# RTM_Connectors.net
KiCad netlist of a schematic drawn in Altium Designer
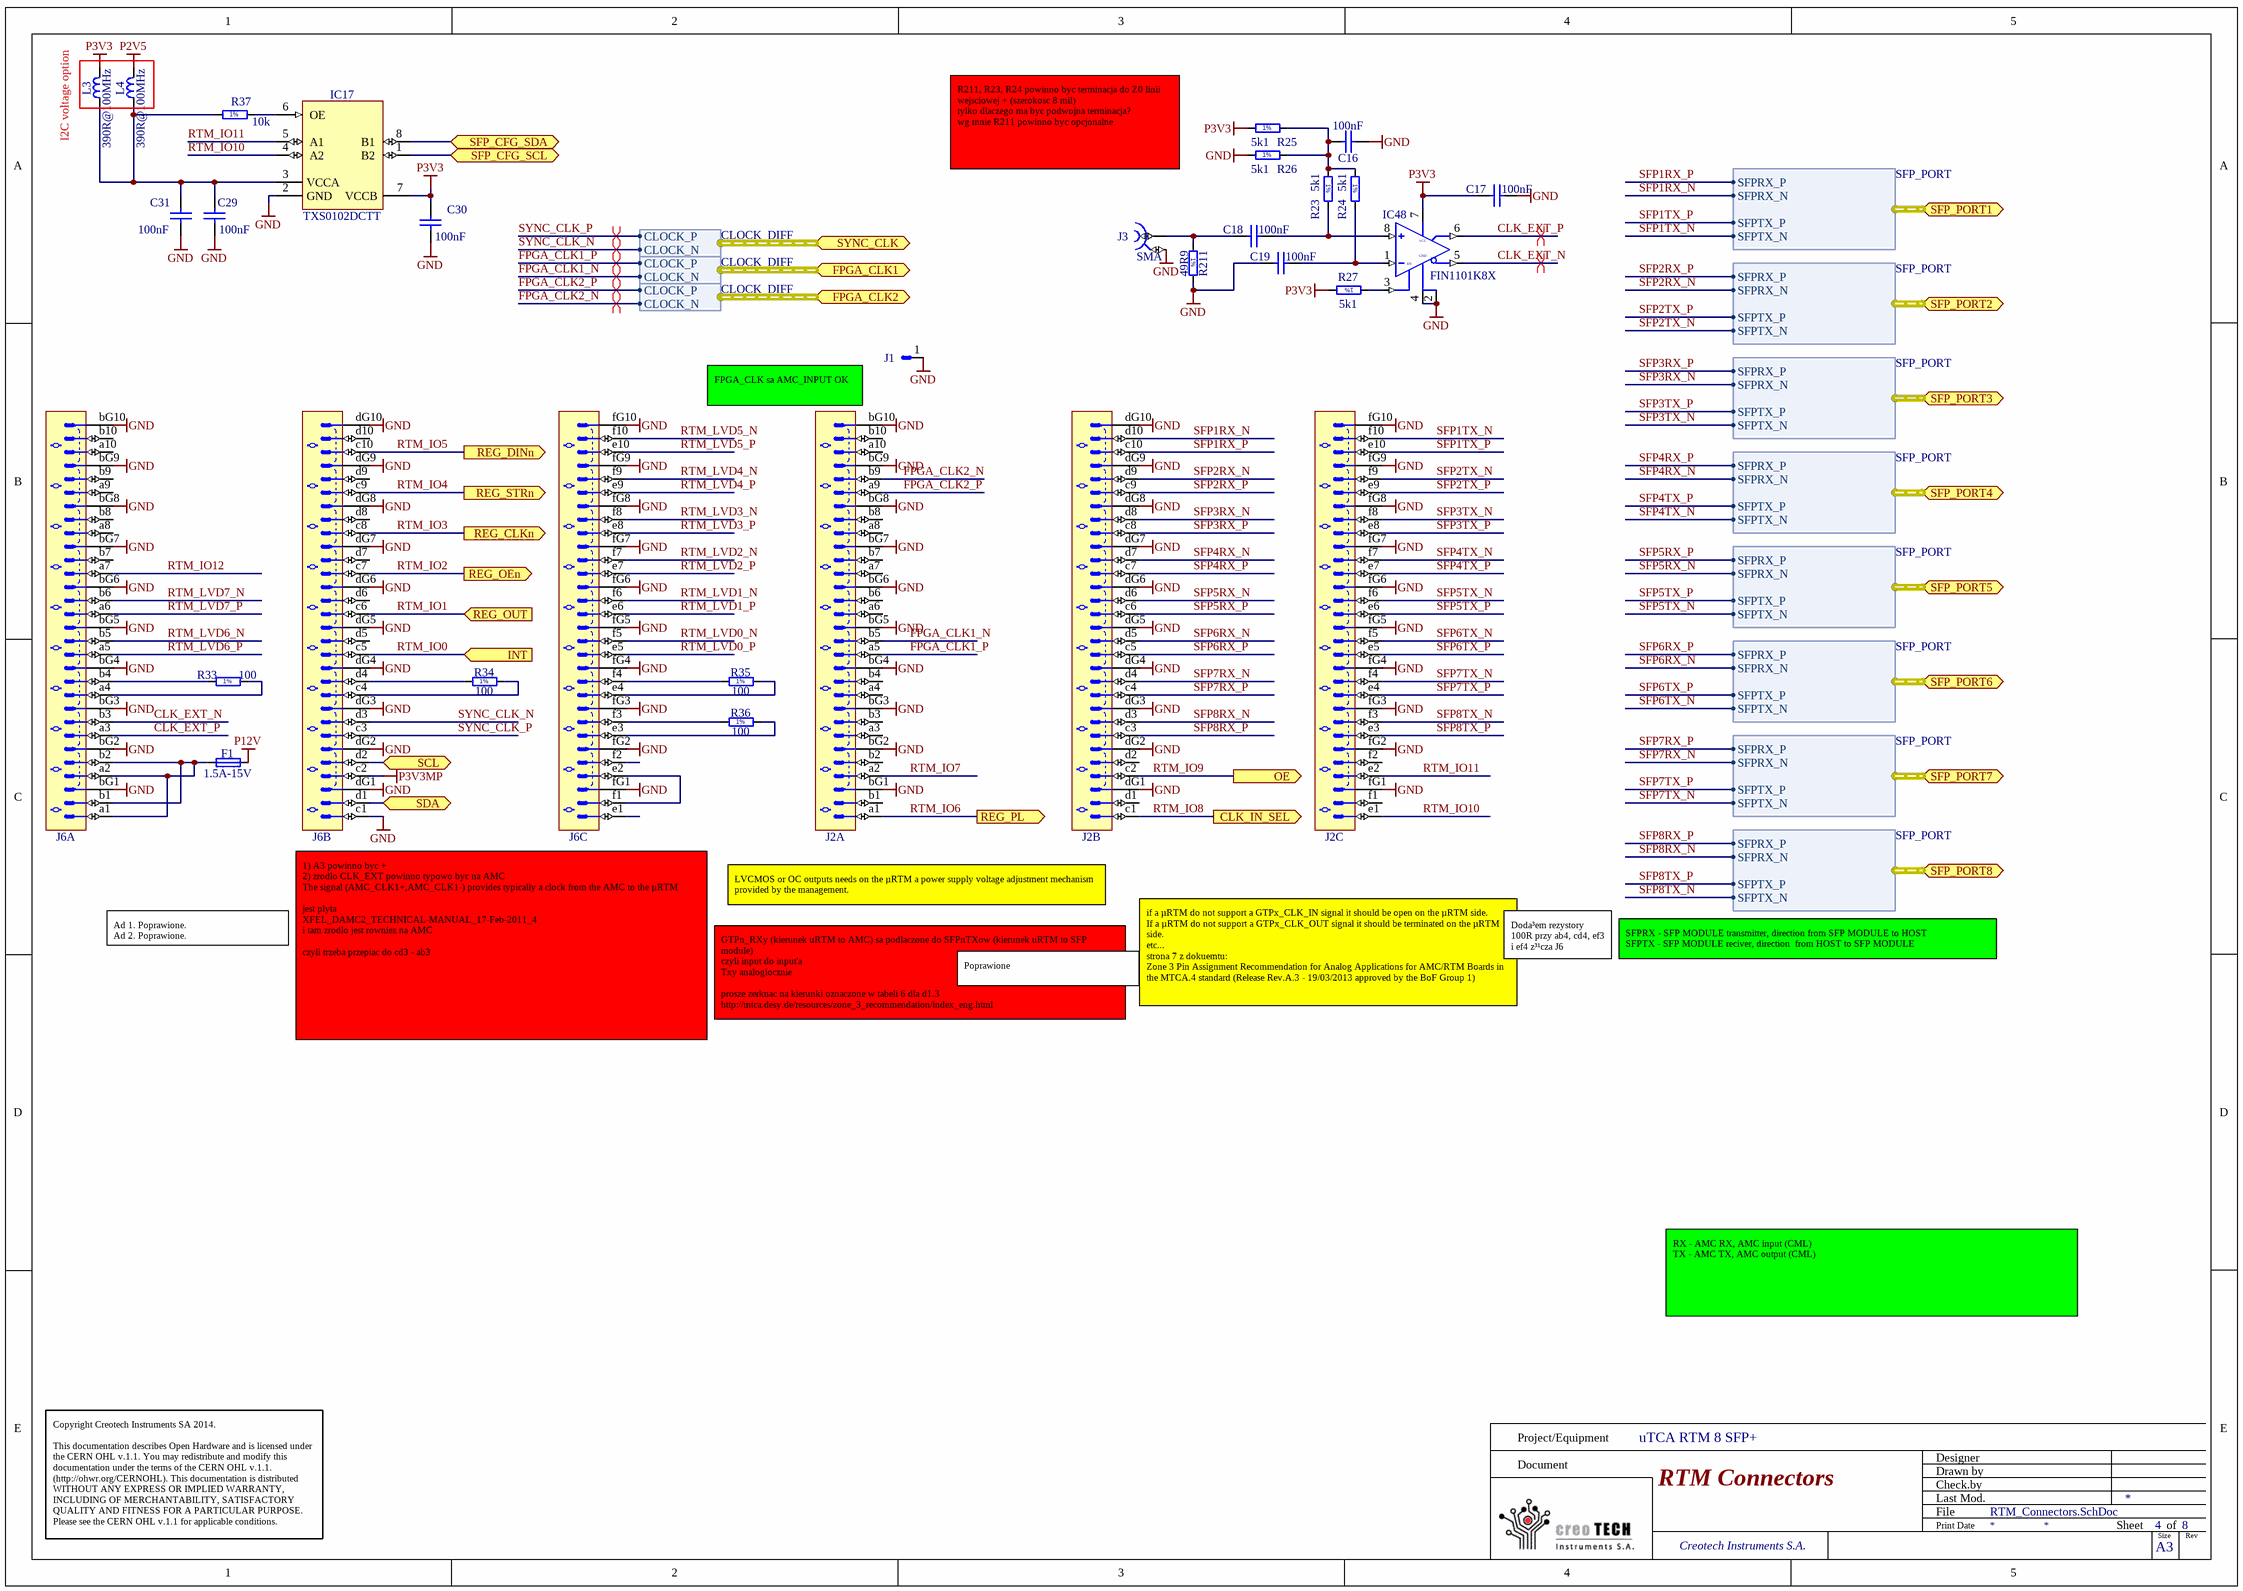
[diagram p0: RTM_Connectors.SchDoc]

(export (version "E")
  (design (tool "Eeschema 10.0.6"))
  (components
    (comp (ref "C16")
      (value "100nF")
      (footprint "CAPC1005X55N")
      (description "Non-polarised capacitor")
      (fields
        (field (name "PART NUMBER") "CC0402_100NF_16V_10%_X7R")
        (field (name "VOLTAGE") "16V")
        (field (name "AUTHOR") "CERN DEM JLC")
      )
      (libsource (lib "Capacitors") (part "Capacitor - non polarized"))
    )
    (comp (ref "C17")
      (value "100nF")
      (footprint "CAPC1005X55N")
      (description "Non-polarised capacitor")
      (fields
        (field (name "PART NUMBER") "CC0402_100NF_16V_10%_X7R")
        (field (name "VOLTAGE") "16V")
        (field (name "AUTHOR") "CERN DEM JLC")
      )
      (libsource (lib "Capacitors") (part "Capacitor - non polarized"))
    )
    (comp (ref "C18")
      (value "100nF")
      (footprint "CAPC1005X55N")
      (description "Non-polarised capacitor")
      (fields
        (field (name "PART NUMBER") "CC0402_100NF_16V_10%_X7R")
        (field (name "VOLTAGE") "16V")
        (field (name "AUTHOR") "CERN DEM JLC")
      )
      (libsource (lib "Capacitors") (part "Capacitor - non polarized"))
    )
    (comp (ref "C19")
      (value "100nF")
      (footprint "CAPC1005X55N")
      (description "Non-polarised capacitor")
      (fields
        (field (name "PART NUMBER") "CC0402_100NF_16V_10%_X7R")
        (field (name "VOLTAGE") "16V")
        (field (name "AUTHOR") "CERN DEM JLC")
      )
      (libsource (lib "Capacitors") (part "Capacitor - non polarized"))
    )
    (comp (ref "C29")
      (value "100nF")
      (footprint "CAPC0603X33N")
      (description "Non-polarised capacitor")
      (fields
        (field (name "PART NUMBER") "CC0201_100NF_6.3V_10%_X5R")
        (field (name "VOLTAGE") "6.3V")
        (field (name "AUTHOR") "CERN DEM JLC")
      )
      (libsource (lib "Capacitors") (part "Capacitor - non polarized"))
    )
    (comp (ref "C30")
      (value "100nF")
      (footprint "CAPC0603X33N")
      (description "Non-polarised capacitor")
      (fields
        (field (name "PART NUMBER") "CC0201_100NF_6.3V_10%_X5R")
        (field (name "VOLTAGE") "6.3V")
        (field (name "AUTHOR") "CERN DEM JLC")
      )
      (libsource (lib "Capacitors") (part "Capacitor - non polarized"))
    )
    (comp (ref "C31")
      (value "100nF")
      (footprint "CAPC0603X33N")
      (description "Non-polarised capacitor")
      (fields
        (field (name "PART NUMBER") "CC0201_100NF_6.3V_10%_X5R")
        (field (name "VOLTAGE") "6.3V")
        (field (name "AUTHOR") "CERN DEM JLC")
      )
      (libsource (lib "Capacitors") (part "Capacitor - non polarized"))
    )
    (comp (ref "F1")
      (value "1.5A-15V")
      (footprint "FUSR_TYCO_SMD150F-2")
      (description "Fuse")
      (fields
        (field (name "PART NUMBER") "FUSR_TYCO_SMD150F-2")
        (field (name "MANUFACTURER") "TYCO ELECTRONICS")
        (field (name "AUTHOR") "CERN DEM JLC")
      )
      (libsource (lib "Eletro-mechanical") (part "Fuse"))
    )
    (comp (ref "IC17")
      (value "TXS0102DCTT")
      (footprint "SOP65P400X130-8N")
      (description "2-Bit Bidirectionnal Voltage-Level Translator for Open-Drain And Push-Pull Applications")
      (fields (field (name "MANUFACTURER") "TEXAS INSTRUMENTS") (field (name "AUTHOR") "CERN DEM JLC"))
      (libsource (lib "ICs And Semiconductors") (part "TXS0102DCT"))
    )
    (comp (ref "IC48")
      (value "FIN1101K8X")
      (footprint "SOP50P310X90-8N")
      (description "LVDS Single Port High Speed Repeater")
      (fields (field (name "MANUFACTURER") "Fairchild") (field (name "AUTHOR") "LNLS DIG GBMB"))
      (libsource (lib "ICs And Semiconductors") (part "FIN1101"))
    )
    (comp (ref "J1")
      (value "~")
      (footprint "TYCO_1469265-1")
      (description "Single Pin Male")
      (fields
        (field (name "PART NUMBER") "TYCO_1469265-1")
        (field (name "MANUFACTURER") "TYCO ELECTRONICS")
        (field (name "AUTHOR") "CERN DEM JLC")
      )
      (libsource (lib "Connectors") (part "Single Pin Male"))
    )
    (comp (ref "J2")
      (value "~")
      (footprint "TYCO_6469183-1")
      (description "Connector 60 ATCA Male 30 Pairs (60 Signals) + 3x10 Ground")
      (fields
        (field (name "PART NUMBER") "TYCO_6469183-1")
        (field (name "MANUFACTURER") "TYCO ELECTRONICS")
        (field (name "AUTHOR") "CERN DEM JLC")
      )
      (libsource (lib "Connectors") (part "Connector ATCA 60+30 Male"))
    )
    (comp (ref "J3")
      (value "SMA")
      (footprint "HUBER-SUHNER_85_SMA-50-0-101/111_NE")
      (fields
        (field (name "PART NUMBER") "HUBER-SUHNER_85_SMA-50-0-101/111_NE")
        (field (name "MANUFACTURER") "HUBER+SUHNER")
        (field (name "MANUFACTURER PART NUMBER") "85_SMA-50-0-101/111_NE")
        (field (name "AUTHOR") "CERN DEM JLC")
      )
      (libsource (lib "Connectors") (part "Coax_1Female_1Shield"))
    )
    (comp (ref "J6")
      (value "~")
      (footprint "TYCO_6469183-1")
      (description "Connector 60 ATCA Male 30 Pairs (60 Signals) + 3x10 Ground")
      (fields
        (field (name "PART NUMBER") "TYCO_6469183-1")
        (field (name "MANUFACTURER") "TYCO ELECTRONICS")
        (field (name "AUTHOR") "CERN DEM JLC")
      )
      (libsource (lib "Connectors") (part "Connector ATCA 60+30 Male"))
    )
    (comp (ref "L3")
      (value "390R@100MHz")
      (footprint "INDC1608X95N")
      (description "Inductor")
      (fields
        (field (name "PART NUMBER") "IND0603_TDK_MPZ1608R391A")
        (field (name "POWER") "1.2A")
        (field (name "AUTHOR") "CERN DEM JLC")
      )
      (libsource (lib "Inductors & Transformers") (part "Inductor"))
    )
    (comp (ref "L4")
      (value "390R@100MHz")
      (footprint "INDC1608X95N")
      (description "Inductor")
      (fields
        (field (name "PART NUMBER") "IND0603_TDK_MPZ1608R391A")
        (field (name "POWER") "1.2A")
        (field (name "AUTHOR") "CERN DEM JLC")
      )
      (libsource (lib "Inductors & Transformers") (part "Inductor"))
    )
    (comp (ref "R23")
      (value "5k1")
      (footprint "RESC1608X55N")
      (description "Resistor - 1%")
      (fields
        (field (name "PART NUMBER") "R0603_5K1_1%_0.1W_100PPM")
        (field (name "POWER") "0.1W")
        (field (name "AUTHOR") "CERN DEM JLC")
      )
      (libsource (lib "Resistors") (part "Resistor - 1%"))
    )
    (comp (ref "R24")
      (value "5k1")
      (footprint "RESC1608X55N")
      (description "Resistor - 1%")
      (fields
        (field (name "PART NUMBER") "R0603_5K1_1%_0.1W_100PPM")
        (field (name "POWER") "0.1W")
        (field (name "AUTHOR") "CERN DEM JLC")
      )
      (libsource (lib "Resistors") (part "Resistor - 1%"))
    )
    (comp (ref "R25")
      (value "5k1")
      (footprint "RESC1608X55N")
      (description "Resistor - 1%")
      (fields
        (field (name "PART NUMBER") "R0603_5K1_1%_0.1W_100PPM")
        (field (name "POWER") "0.1W")
        (field (name "AUTHOR") "CERN DEM JLC")
      )
      (libsource (lib "Resistors") (part "Resistor - 1%"))
    )
    (comp (ref "R26")
      (value "5k1")
      (footprint "RESC1608X55N")
      (description "Resistor - 1%")
      (fields
        (field (name "PART NUMBER") "R0603_5K1_1%_0.1W_100PPM")
        (field (name "POWER") "0.1W")
        (field (name "AUTHOR") "CERN DEM JLC")
      )
      (libsource (lib "Resistors") (part "Resistor - 1%"))
    )
    (comp (ref "R27")
      (value "5k1")
      (footprint "RESC1608X55N")
      (description "Resistor - 1%")
      (fields
        (field (name "PART NUMBER") "R0603_5K1_1%_0.1W_100PPM")
        (field (name "POWER") "0.1W")
        (field (name "AUTHOR") "CERN DEM JLC")
      )
      (libsource (lib "Resistors") (part "Resistor - 1%"))
    )
    (comp (ref "R33")
      (value "100")
      (footprint "RESC1608X55N")
      (description "Resistor - 1%")
      (fields
        (field (name "PART NUMBER") "R0603_100R_1%_0.1W_100PPM")
        (field (name "POWER") "0.1W")
        (field (name "AUTHOR") "CERN DEM JLC")
      )
      (libsource (lib "Resistors") (part "Resistor - 1%"))
    )
    (comp (ref "R34")
      (value "100")
      (footprint "RESC1608X55N")
      (description "Resistor - 1%")
      (fields
        (field (name "PART NUMBER") "R0603_100R_1%_0.1W_100PPM")
        (field (name "POWER") "0.1W")
        (field (name "AUTHOR") "CERN DEM JLC")
      )
      (libsource (lib "Resistors") (part "Resistor - 1%"))
    )
    (comp (ref "R35")
      (value "100")
      (footprint "RESC1608X55N")
      (description "Resistor - 1%")
      (fields
        (field (name "PART NUMBER") "R0603_100R_1%_0.1W_100PPM")
        (field (name "POWER") "0.1W")
        (field (name "AUTHOR") "CERN DEM JLC")
      )
      (libsource (lib "Resistors") (part "Resistor - 1%"))
    )
    (comp (ref "R36")
      (value "100")
      (footprint "RESC1608X55N")
      (description "Resistor - 1%")
      (fields
        (field (name "PART NUMBER") "R0603_100R_1%_0.1W_100PPM")
        (field (name "POWER") "0.1W")
        (field (name "AUTHOR") "CERN DEM JLC")
      )
      (libsource (lib "Resistors") (part "Resistor - 1%"))
    )
    (comp (ref "R37")
      (value "10k")
      (footprint "RESC1005X40N")
      (description "Resistor - 1%")
      (fields
        (field (name "PART NUMBER") "R0402_10K_1%_0.0625W_100PPM")
        (field (name "POWER") "0.0625W")
        (field (name "AUTHOR") "CERN DEM JLC")
      )
      (libsource (lib "Resistors") (part "Resistor - 1%"))
    )
    (comp (ref "R211")
      (value "49R9")
      (footprint "RESC1005X40N")
      (description "Resistor - 1%")
      (fields
        (field (name "PART NUMBER") "R0402_49R9_1%_0.0625W_100PPM")
        (field (name "POWER") "0.0625W")
        (field (name "AUTHOR") "CERN DEM JLC")
      )
      (libsource (lib "Resistors") (part "Resistor - 1%"))
    )
  )
  (nets
    (net (code "3") (name "/CLK_EXT_N") (class "Default")
      (node (ref "IC48") (pin "5") (pinfunction "~{Q}_5") (pintype "output"))
      (node (ref "J6") (pin "b3") (pinfunction "b3_b3") (pintype "bidirectional"))
    )
    (net (code "4") (name "/CLK_EXT_P") (class "Default")
      (node (ref "IC48") (pin "6") (pinfunction "Q_6") (pintype "output"))
      (node (ref "J6") (pin "a3") (pinfunction "a3_a3") (pintype "bidirectional"))
    )
    (net (code "5") (name "/FPGA_CLK1_N") (class "Default")
      (node (ref "J2") (pin "b5") (pinfunction "b5_b5") (pintype "bidirectional"))
    )
    (net (code "6") (name "/FPGA_CLK1_P") (class "Default")
      (node (ref "J2") (pin "a5") (pinfunction "a5_a5") (pintype "bidirectional"))
    )
    (net (code "7") (name "/FPGA_CLK2_N") (class "Default")
      (node (ref "J2") (pin "b9") (pinfunction "b9_b9") (pintype "bidirectional"))
    )
    (net (code "8") (name "/FPGA_CLK2_P") (class "Default")
      (node (ref "J2") (pin "a9") (pinfunction "a9_a9") (pintype "bidirectional"))
    )
    (net (code "9") (name "/RTM_IO0") (class "Default")
      (node (ref "J6") (pin "c5") (pinfunction "c5_c5") (pintype "bidirectional"))
    )
    (net (code "10") (name "/RTM_IO1") (class "Default")
      (node (ref "J6") (pin "c6") (pinfunction "c6_c6") (pintype "bidirectional"))
    )
    (net (code "11") (name "/RTM_IO2") (class "Default")
      (node (ref "J6") (pin "c7") (pinfunction "c7_c7") (pintype "bidirectional"))
    )
    (net (code "12") (name "/RTM_IO3") (class "Default")
      (node (ref "J6") (pin "c8") (pinfunction "c8_c8") (pintype "bidirectional"))
    )
    (net (code "13") (name "/RTM_IO4") (class "Default")
      (node (ref "J6") (pin "c9") (pinfunction "c9_c9") (pintype "bidirectional"))
    )
    (net (code "14") (name "/RTM_IO5") (class "Default")
      (node (ref "J6") (pin "c10") (pinfunction "c10_c10") (pintype "bidirectional"))
    )
    (net (code "15") (name "/RTM_IO6") (class "Default")
      (node (ref "J2") (pin "a1") (pinfunction "a1_a1") (pintype "bidirectional"))
    )
    (net (code "16") (name "/RTM_IO7") (class "Default")
      (node (ref "J2") (pin "a2") (pinfunction "a2_a2") (pintype "bidirectional"))
    )
    (net (code "17") (name "/RTM_IO8") (class "Default")
      (node (ref "J2") (pin "c1") (pinfunction "c1_c1") (pintype "bidirectional"))
    )
    (net (code "18") (name "/RTM_IO9") (class "Default")
      (node (ref "J2") (pin "c2") (pinfunction "c2_c2") (pintype "bidirectional"))
    )
    (net (code "19") (name "/RTM_IO10") (class "Default")
      (node (ref "IC17") (pin "4") (pinfunction "A2_4") (pintype "bidirectional"))
      (node (ref "J2") (pin "e1") (pinfunction "e1_e1") (pintype "bidirectional"))
    )
    (net (code "20") (name "/RTM_IO11") (class "Default")
      (node (ref "IC17") (pin "5") (pinfunction "A1_5") (pintype "bidirectional"))
      (node (ref "J2") (pin "e2") (pinfunction "e2_e2") (pintype "bidirectional"))
    )
    (net (code "21") (name "/RTM_IO12") (class "Default")
      (node (ref "J6") (pin "a7") (pinfunction "a7_a7") (pintype "bidirectional"))
    )
    (net (code "22") (name "/RTM_LVD0_N") (class "Default")
      (node (ref "J6") (pin "f5") (pinfunction "f5_f5") (pintype "bidirectional"))
    )
    (net (code "23") (name "/RTM_LVD0_P") (class "Default")
      (node (ref "J6") (pin "e5") (pinfunction "e5_e5") (pintype "bidirectional"))
    )
    (net (code "24") (name "/RTM_LVD1_N") (class "Default")
      (node (ref "J6") (pin "f6") (pinfunction "f6_f6") (pintype "bidirectional"))
    )
    (net (code "25") (name "/RTM_LVD1_P") (class "Default")
      (node (ref "J6") (pin "e6") (pinfunction "e6_e6") (pintype "bidirectional"))
    )
    (net (code "26") (name "/RTM_LVD2_N") (class "Default")
      (node (ref "J6") (pin "f7") (pinfunction "f7_f7") (pintype "bidirectional"))
    )
    (net (code "27") (name "/RTM_LVD2_P") (class "Default")
      (node (ref "J6") (pin "e7") (pinfunction "e7_e7") (pintype "bidirectional"))
    )
    (net (code "28") (name "/RTM_LVD3_N") (class "Default")
      (node (ref "J6") (pin "f8") (pinfunction "f8_f8") (pintype "bidirectional"))
    )
    (net (code "29") (name "/RTM_LVD3_P") (class "Default")
      (node (ref "J6") (pin "e8") (pinfunction "e8_e8") (pintype "bidirectional"))
    )
    (net (code "30") (name "/RTM_LVD4_N") (class "Default")
      (node (ref "J6") (pin "f9") (pinfunction "f9_f9") (pintype "bidirectional"))
    )
    (net (code "31") (name "/RTM_LVD4_P") (class "Default")
      (node (ref "J6") (pin "e9") (pinfunction "e9_e9") (pintype "bidirectional"))
    )
    (net (code "32") (name "/RTM_LVD5_N") (class "Default")
      (node (ref "J6") (pin "f10") (pinfunction "f10_f10") (pintype "bidirectional"))
    )
    (net (code "33") (name "/RTM_LVD5_P") (class "Default")
      (node (ref "J6") (pin "e10") (pinfunction "e10_e10") (pintype "bidirectional"))
    )
    (net (code "34") (name "/RTM_LVD6_N") (class "Default")
      (node (ref "J6") (pin "b5") (pinfunction "b5_b5") (pintype "bidirectional"))
    )
    (net (code "35") (name "/RTM_LVD6_P") (class "Default")
      (node (ref "J6") (pin "a5") (pinfunction "a5_a5") (pintype "bidirectional"))
    )
    (net (code "36") (name "/RTM_LVD7_N") (class "Default")
      (node (ref "J6") (pin "b6") (pinfunction "b6_b6") (pintype "bidirectional"))
    )
    (net (code "37") (name "/RTM_LVD7_P") (class "Default")
      (node (ref "J6") (pin "a6") (pinfunction "a6_a6") (pintype "bidirectional"))
    )
    (net (code "38") (name "/SCL") (class "Default")
      (node (ref "J6") (pin "d2") (pinfunction "d2_d2") (pintype "bidirectional"))
    )
    (net (code "39") (name "/SDA") (class "Default")
      (node (ref "J6") (pin "d1") (pinfunction "d1_d1") (pintype "bidirectional"))
    )
    (net (code "40") (name "/SFP1RX_N") (class "Default")
      (node (ref "J2") (pin "d10") (pinfunction "d10_d10") (pintype "bidirectional"))
    )
    (net (code "41") (name "/SFP1RX_P") (class "Default")
      (node (ref "J2") (pin "c10") (pinfunction "c10_c10") (pintype "bidirectional"))
    )
    (net (code "42") (name "/SFP1TX_N") (class "Default")
      (node (ref "J2") (pin "f10") (pinfunction "f10_f10") (pintype "bidirectional"))
    )
    (net (code "43") (name "/SFP1TX_P") (class "Default")
      (node (ref "J2") (pin "e10") (pinfunction "e10_e10") (pintype "bidirectional"))
    )
    (net (code "44") (name "/SFP2RX_N") (class "Default")
      (node (ref "J2") (pin "d9") (pinfunction "d9_d9") (pintype "bidirectional"))
    )
    (net (code "45") (name "/SFP2RX_P") (class "Default")
      (node (ref "J2") (pin "c9") (pinfunction "c9_c9") (pintype "bidirectional"))
    )
    (net (code "46") (name "/SFP2TX_N") (class "Default")
      (node (ref "J2") (pin "f9") (pinfunction "f9_f9") (pintype "bidirectional"))
    )
    (net (code "47") (name "/SFP2TX_P") (class "Default")
      (node (ref "J2") (pin "e9") (pinfunction "e9_e9") (pintype "bidirectional"))
    )
    (net (code "48") (name "/SFP3RX_N") (class "Default")
      (node (ref "J2") (pin "d8") (pinfunction "d8_d8") (pintype "bidirectional"))
    )
    (net (code "49") (name "/SFP3RX_P") (class "Default")
      (node (ref "J2") (pin "c8") (pinfunction "c8_c8") (pintype "bidirectional"))
    )
    (net (code "50") (name "/SFP3TX_N") (class "Default")
      (node (ref "J2") (pin "f8") (pinfunction "f8_f8") (pintype "bidirectional"))
    )
    (net (code "51") (name "/SFP3TX_P") (class "Default")
      (node (ref "J2") (pin "e8") (pinfunction "e8_e8") (pintype "bidirectional"))
    )
    (net (code "52") (name "/SFP4RX_N") (class "Default")
      (node (ref "J2") (pin "d7") (pinfunction "d7_d7") (pintype "bidirectional"))
    )
    (net (code "53") (name "/SFP4RX_P") (class "Default")
      (node (ref "J2") (pin "c7") (pinfunction "c7_c7") (pintype "bidirectional"))
    )
    (net (code "54") (name "/SFP4TX_N") (class "Default")
      (node (ref "J2") (pin "f7") (pinfunction "f7_f7") (pintype "bidirectional"))
    )
    (net (code "55") (name "/SFP4TX_P") (class "Default")
      (node (ref "J2") (pin "e7") (pinfunction "e7_e7") (pintype "bidirectional"))
    )
    (net (code "56") (name "/SFP5RX_N") (class "Default")
      (node (ref "J2") (pin "d6") (pinfunction "d6_d6") (pintype "bidirectional"))
    )
    (net (code "57") (name "/SFP5RX_P") (class "Default")
      (node (ref "J2") (pin "c6") (pinfunction "c6_c6") (pintype "bidirectional"))
    )
    (net (code "58") (name "/SFP5TX_N") (class "Default")
      (node (ref "J2") (pin "f6") (pinfunction "f6_f6") (pintype "bidirectional"))
    )
    (net (code "59") (name "/SFP5TX_P") (class "Default")
      (node (ref "J2") (pin "e6") (pinfunction "e6_e6") (pintype "bidirectional"))
    )
    (net (code "60") (name "/SFP6RX_N") (class "Default")
      (node (ref "J2") (pin "d5") (pinfunction "d5_d5") (pintype "bidirectional"))
    )
    (net (code "61") (name "/SFP6RX_P") (class "Default")
      (node (ref "J2") (pin "c5") (pinfunction "c5_c5") (pintype "bidirectional"))
    )
    (net (code "62") (name "/SFP6TX_N") (class "Default")
      (node (ref "J2") (pin "f5") (pinfunction "f5_f5") (pintype "bidirectional"))
    )
    (net (code "63") (name "/SFP6TX_P") (class "Default")
      (node (ref "J2") (pin "e5") (pinfunction "e5_e5") (pintype "bidirectional"))
    )
    (net (code "64") (name "/SFP7RX_N") (class "Default")
      (node (ref "J2") (pin "d4") (pinfunction "d4_d4") (pintype "bidirectional"))
    )
    (net (code "65") (name "/SFP7RX_P") (class "Default")
      (node (ref "J2") (pin "c4") (pinfunction "c4_c4") (pintype "bidirectional"))
    )
    (net (code "66") (name "/SFP7TX_N") (class "Default")
      (node (ref "J2") (pin "f4") (pinfunction "f4_f4") (pintype "bidirectional"))
    )
    (net (code "67") (name "/SFP7TX_P") (class "Default")
      (node (ref "J2") (pin "e4") (pinfunction "e4_e4") (pintype "bidirectional"))
    )
    (net (code "68") (name "/SFP8RX_N") (class "Default")
      (node (ref "J2") (pin "d3") (pinfunction "d3_d3") (pintype "bidirectional"))
    )
    (net (code "69") (name "/SFP8RX_P") (class "Default")
      (node (ref "J2") (pin "c3") (pinfunction "c3_c3") (pintype "bidirectional"))
    )
    (net (code "70") (name "/SFP8TX_N") (class "Default")
      (node (ref "J2") (pin "f3") (pinfunction "f3_f3") (pintype "bidirectional"))
    )
    (net (code "71") (name "/SFP8TX_P") (class "Default")
      (node (ref "J2") (pin "e3") (pinfunction "e3_e3") (pintype "bidirectional"))
    )
    (net (code "72") (name "/SFP_CFG_SCL") (class "Default")
      (node (ref "IC17") (pin "1") (pinfunction "B2_1") (pintype "bidirectional"))
    )
    (net (code "73") (name "/SFP_CFG_SDA") (class "Default")
      (node (ref "IC17") (pin "8") (pinfunction "B1_8") (pintype "bidirectional"))
    )
    (net (code "74") (name "/SYNC_CLK_N") (class "Default")
      (node (ref "J6") (pin "d3") (pinfunction "d3_d3") (pintype "bidirectional"))
    )
    (net (code "75") (name "/SYNC_CLK_P") (class "Default")
      (node (ref "J6") (pin "c3") (pinfunction "c3_c3") (pintype "bidirectional"))
    )
    (net (code "78") (name "GND") (class "Default")
      (node (ref "C16") (pin "2") (pinfunction "2_2") (pintype "passive"))
      (node (ref "C17") (pin "2") (pinfunction "2_2") (pintype "passive"))
      (node (ref "C19") (pin "1") (pinfunction "1_1") (pintype "passive"))
      (node (ref "C29") (pin "2") (pinfunction "2_2") (pintype "passive"))
      (node (ref "C30") (pin "2") (pinfunction "2_2") (pintype "passive"))
      (node (ref "C31") (pin "2") (pinfunction "2_2") (pintype "passive"))
      (node (ref "IC17") (pin "2") (pinfunction "GND_2") (pintype "power_in"))
      (node (ref "IC48") (pin "2") (pinfunction "GND_2") (pintype "power_in"))
      (node (ref "IC48") (pin "4") (pinfunction "GND_4") (pintype "power_in"))
      (node (ref "J1") (pin "1") (pinfunction "1_1") (pintype "bidirectional"))
      (node (ref "J2") (pin "bG1") (pinfunction "bG1_bG1") (pintype "power_in"))
      (node (ref "J2") (pin "bG10") (pinfunction "bG10_bG10") (pintype "power_in"))
      (node (ref "J2") (pin "bG2") (pinfunction "bG2_bG2") (pintype "power_in"))
      (node (ref "J2") (pin "bG3") (pinfunction "bG3_bG3") (pintype "power_in"))
      (node (ref "J2") (pin "bG4") (pinfunction "bG4_bG4") (pintype "power_in"))
      (node (ref "J2") (pin "bG5") (pinfunction "bG5_bG5") (pintype "power_in"))
      (node (ref "J2") (pin "bG6") (pinfunction "bG6_bG6") (pintype "power_in"))
      (node (ref "J2") (pin "bG7") (pinfunction "bG7_bG7") (pintype "power_in"))
      (node (ref "J2") (pin "bG8") (pinfunction "bG8_bG8") (pintype "power_in"))
      (node (ref "J2") (pin "bG9") (pinfunction "bG9_bG9") (pintype "power_in"))
      (node (ref "J2") (pin "dG1") (pinfunction "dG1_dG1") (pintype "power_in"))
      (node (ref "J2") (pin "dG10") (pinfunction "dG10_dG10") (pintype "power_in"))
      (node (ref "J2") (pin "dG2") (pinfunction "dG2_dG2") (pintype "power_in"))
      (node (ref "J2") (pin "dG3") (pinfunction "dG3_dG3") (pintype "power_in"))
      (node (ref "J2") (pin "dG4") (pinfunction "dG4_dG4") (pintype "power_in"))
      (node (ref "J2") (pin "dG5") (pinfunction "dG5_dG5") (pintype "power_in"))
      (node (ref "J2") (pin "dG6") (pinfunction "dG6_dG6") (pintype "power_in"))
      (node (ref "J2") (pin "dG7") (pinfunction "dG7_dG7") (pintype "power_in"))
      (node (ref "J2") (pin "dG8") (pinfunction "dG8_dG8") (pintype "power_in"))
      (node (ref "J2") (pin "dG9") (pinfunction "dG9_dG9") (pintype "power_in"))
      (node (ref "J2") (pin "fG1") (pinfunction "fG1_fG1") (pintype "power_in"))
      (node (ref "J2") (pin "fG10") (pinfunction "fG10_fG10") (pintype "power_in"))
      (node (ref "J2") (pin "fG2") (pinfunction "fG2_fG2") (pintype "power_in"))
      (node (ref "J2") (pin "fG3") (pinfunction "fG3_fG3") (pintype "power_in"))
      (node (ref "J2") (pin "fG4") (pinfunction "fG4_fG4") (pintype "power_in"))
      (node (ref "J2") (pin "fG5") (pinfunction "fG5_fG5") (pintype "power_in"))
      (node (ref "J2") (pin "fG6") (pinfunction "fG6_fG6") (pintype "power_in"))
      (node (ref "J2") (pin "fG7") (pinfunction "fG7_fG7") (pintype "power_in"))
      (node (ref "J2") (pin "fG8") (pinfunction "fG8_fG8") (pintype "power_in"))
      (node (ref "J2") (pin "fG9") (pinfunction "fG9_fG9") (pintype "power_in"))
      (node (ref "J3") (pin "2") (pinfunction "2_2") (pintype "bidirectional"))
      (node (ref "J6") (pin "bG1") (pinfunction "bG1_bG1") (pintype "power_in"))
      (node (ref "J6") (pin "bG10") (pinfunction "bG10_bG10") (pintype "power_in"))
      (node (ref "J6") (pin "bG2") (pinfunction "bG2_bG2") (pintype "power_in"))
      (node (ref "J6") (pin "bG3") (pinfunction "bG3_bG3") (pintype "power_in"))
      (node (ref "J6") (pin "bG4") (pinfunction "bG4_bG4") (pintype "power_in"))
      (node (ref "J6") (pin "bG5") (pinfunction "bG5_bG5") (pintype "power_in"))
      (node (ref "J6") (pin "bG6") (pinfunction "bG6_bG6") (pintype "power_in"))
      (node (ref "J6") (pin "bG7") (pinfunction "bG7_bG7") (pintype "power_in"))
      (node (ref "J6") (pin "bG8") (pinfunction "bG8_bG8") (pintype "power_in"))
      (node (ref "J6") (pin "bG9") (pinfunction "bG9_bG9") (pintype "power_in"))
      (node (ref "J6") (pin "c1") (pinfunction "c1_c1") (pintype "bidirectional"))
      (node (ref "J6") (pin "dG1") (pinfunction "dG1_dG1") (pintype "power_in"))
      (node (ref "J6") (pin "dG10") (pinfunction "dG10_dG10") (pintype "power_in"))
      (node (ref "J6") (pin "dG2") (pinfunction "dG2_dG2") (pintype "power_in"))
      (node (ref "J6") (pin "dG3") (pinfunction "dG3_dG3") (pintype "power_in"))
      (node (ref "J6") (pin "dG4") (pinfunction "dG4_dG4") (pintype "power_in"))
      (node (ref "J6") (pin "dG5") (pinfunction "dG5_dG5") (pintype "power_in"))
      (node (ref "J6") (pin "dG6") (pinfunction "dG6_dG6") (pintype "power_in"))
      (node (ref "J6") (pin "dG7") (pinfunction "dG7_dG7") (pintype "power_in"))
      (node (ref "J6") (pin "dG8") (pinfunction "dG8_dG8") (pintype "power_in"))
      (node (ref "J6") (pin "dG9") (pinfunction "dG9_dG9") (pintype "power_in"))
      (node (ref "J6") (pin "fG1") (pinfunction "fG1_fG1") (pintype "power_in"))
      (node (ref "J6") (pin "fG10") (pinfunction "fG10_fG10") (pintype "power_in"))
      (node (ref "J6") (pin "fG2") (pinfunction "fG2_fG2") (pintype "power_in"))
      (node (ref "J6") (pin "fG3") (pinfunction "fG3_fG3") (pintype "power_in"))
      (node (ref "J6") (pin "fG4") (pinfunction "fG4_fG4") (pintype "power_in"))
      (node (ref "J6") (pin "fG5") (pinfunction "fG5_fG5") (pintype "power_in"))
      (node (ref "J6") (pin "fG6") (pinfunction "fG6_fG6") (pintype "power_in"))
      (node (ref "J6") (pin "fG7") (pinfunction "fG7_fG7") (pintype "power_in"))
      (node (ref "J6") (pin "fG8") (pinfunction "fG8_fG8") (pintype "power_in"))
      (node (ref "J6") (pin "fG9") (pinfunction "fG9_fG9") (pintype "power_in"))
      (node (ref "R211") (pin "2") (pinfunction "2_2") (pintype "passive"))
      (node (ref "R26") (pin "1") (pinfunction "1_1") (pintype "passive"))
    )
    (net (code "79") (name "Net-(C16-Pad1)") (class "Default")
      (node (ref "C16") (pin "1") (pinfunction "1_1") (pintype "passive"))
      (node (ref "R23") (pin "1") (pinfunction "1_1") (pintype "passive"))
      (node (ref "R24") (pin "1") (pinfunction "1_1") (pintype "passive"))
      (node (ref "R25") (pin "2") (pinfunction "2_2") (pintype "passive"))
      (node (ref "R26") (pin "2") (pinfunction "2_2") (pintype "passive"))
    )
    (net (code "80") (name "Net-(C18-Pad1)") (class "Default")
      (node (ref "C18") (pin "1") (pinfunction "1_1") (pintype "passive"))
      (node (ref "J3") (pin "1") (pinfunction "1_1") (pintype "bidirectional"))
      (node (ref "R211") (pin "1") (pinfunction "1_1") (pintype "passive"))
    )
    (net (code "81") (name "Net-(C18-Pad2)") (class "Default")
      (node (ref "C18") (pin "2") (pinfunction "2_2") (pintype "passive"))
      (node (ref "IC48") (pin "8") (pinfunction "IN_8") (pintype "input"))
      (node (ref "R23") (pin "2") (pinfunction "2_2") (pintype "passive"))
    )
    (net (code "82") (name "Net-(C19-Pad2)") (class "Default")
      (node (ref "C19") (pin "2") (pinfunction "2_2") (pintype "passive"))
      (node (ref "IC48") (pin "1") (pinfunction "IN_1") (pintype "input"))
      (node (ref "R24") (pin "2") (pinfunction "2_2") (pintype "passive"))
    )
    (net (code "83") (name "Net-(F1-Pad1)") (class "Default")
      (node (ref "F1") (pin "1") (pinfunction "1_1") (pintype "passive"))
      (node (ref "J6") (pin "a1") (pinfunction "a1_a1") (pintype "bidirectional"))
      (node (ref "J6") (pin "a2") (pinfunction "a2_a2") (pintype "bidirectional"))
      (node (ref "J6") (pin "b1") (pinfunction "b1_b1") (pintype "bidirectional"))
      (node (ref "J6") (pin "b2") (pinfunction "b2_b2") (pintype "bidirectional"))
    )
    (net (code "84") (name "Net-(IC17-OE)") (class "Default")
      (node (ref "IC17") (pin "6") (pinfunction "OE_6") (pintype "input"))
      (node (ref "R37") (pin "2") (pinfunction "2_2") (pintype "passive"))
    )
    (net (code "85") (name "Net-(IC17-Vcca)") (class "Default")
      (node (ref "C29") (pin "1") (pinfunction "1_1") (pintype "passive"))
      (node (ref "C31") (pin "1") (pinfunction "1_1") (pintype "passive"))
      (node (ref "IC17") (pin "3") (pinfunction "Vcca_3") (pintype "power_in"))
      (node (ref "L3") (pin "1") (pinfunction "1_1") (pintype "passive"))
      (node (ref "L4") (pin "1") (pinfunction "1_1") (pintype "passive"))
      (node (ref "R37") (pin "1") (pinfunction "1_1") (pintype "passive"))
    )
    (net (code "86") (name "Net-(IC48-EN)") (class "Default")
      (node (ref "IC48") (pin "3") (pinfunction "EN_3") (pintype "input"))
      (node (ref "R27") (pin "1") (pinfunction "1_1") (pintype "passive"))
    )
    (net (code "87") (name "Net-(J6-Pada4)") (class "Default")
      (node (ref "J6") (pin "a4") (pinfunction "a4_a4") (pintype "bidirectional"))
      (node (ref "R33") (pin "2") (pinfunction "2_2") (pintype "passive"))
    )
    (net (code "88") (name "Net-(J6-Padb4)") (class "Default")
      (node (ref "J6") (pin "b4") (pinfunction "b4_b4") (pintype "bidirectional"))
      (node (ref "R33") (pin "1") (pinfunction "1_1") (pintype "passive"))
    )
    (net (code "89") (name "Net-(J6-Padc4)") (class "Default")
      (node (ref "J6") (pin "c4") (pinfunction "c4_c4") (pintype "bidirectional"))
      (node (ref "R34") (pin "2") (pinfunction "2_2") (pintype "passive"))
    )
    (net (code "90") (name "Net-(J6-Padd4)") (class "Default")
      (node (ref "J6") (pin "d4") (pinfunction "d4_d4") (pintype "bidirectional"))
      (node (ref "R34") (pin "1") (pinfunction "1_1") (pintype "passive"))
    )
    (net (code "91") (name "Net-(J6-Pade2)") (class "Default")
      (node (ref "J6") (pin "e2") (pinfunction "e2_e2") (pintype "bidirectional"))
      (node (ref "J6") (pin "f1") (pinfunction "f1_f1") (pintype "bidirectional"))
    )
    (net (code "92") (name "Net-(J6-Pade3)") (class "Default")
      (node (ref "J6") (pin "e3") (pinfunction "e3_e3") (pintype "bidirectional"))
      (node (ref "R36") (pin "2") (pinfunction "2_2") (pintype "passive"))
    )
    (net (code "93") (name "Net-(J6-Pade4)") (class "Default")
      (node (ref "J6") (pin "e4") (pinfunction "e4_e4") (pintype "bidirectional"))
      (node (ref "R35") (pin "2") (pinfunction "2_2") (pintype "passive"))
    )
    (net (code "94") (name "Net-(J6-Padf3)") (class "Default")
      (node (ref "J6") (pin "f3") (pinfunction "f3_f3") (pintype "bidirectional"))
      (node (ref "R36") (pin "1") (pinfunction "1_1") (pintype "passive"))
    )
    (net (code "95") (name "Net-(J6-Padf4)") (class "Default")
      (node (ref "J6") (pin "f4") (pinfunction "f4_f4") (pintype "bidirectional"))
      (node (ref "R35") (pin "1") (pinfunction "1_1") (pintype "passive"))
    )
    (net (code "96") (name "P2V5") (class "Default")
      (node (ref "L4") (pin "2") (pinfunction "2_2") (pintype "passive"))
    )
    (net (code "97") (name "P3V3") (class "Default")
      (node (ref "C17") (pin "1") (pinfunction "1_1") (pintype "passive"))
      (node (ref "C30") (pin "1") (pinfunction "1_1") (pintype "passive"))
      (node (ref "IC17") (pin "7") (pinfunction "Vccb_7") (pintype "power_in"))
      (node (ref "IC48") (pin "7") (pinfunction "VCC_7") (pintype "power_in"))
      (node (ref "L3") (pin "2") (pinfunction "2_2") (pintype "passive"))
      (node (ref "R25") (pin "1") (pinfunction "1_1") (pintype "passive"))
      (node (ref "R27") (pin "2") (pinfunction "2_2") (pintype "passive"))
    )
    (net (code "98") (name "P3V3MP") (class "Default")
      (node (ref "J6") (pin "c2") (pinfunction "c2_c2") (pintype "bidirectional"))
    )
    (net (code "99") (name "P12V") (class "Default")
      (node (ref "F1") (pin "2") (pinfunction "2_2") (pintype "passive"))
    )
    (net (code "100") (name "unconnected-(J2-Pada3)") (class "Default")
      (node (ref "J2") (pin "a3") (pinfunction "a3_a3") (pintype "bidirectional"))
    )
    (net (code "101") (name "unconnected-(J2-Pada4)") (class "Default")
      (node (ref "J2") (pin "a4") (pinfunction "a4_a4") (pintype "bidirectional"))
    )
    (net (code "102") (name "unconnected-(J2-Pada6)") (class "Default")
      (node (ref "J2") (pin "a6") (pinfunction "a6_a6") (pintype "bidirectional"))
    )
    (net (code "103") (name "unconnected-(J2-Pada7)") (class "Default")
      (node (ref "J2") (pin "a7") (pinfunction "a7_a7") (pintype "bidirectional"))
    )
    (net (code "104") (name "unconnected-(J2-Pada8)") (class "Default")
      (node (ref "J2") (pin "a8") (pinfunction "a8_a8") (pintype "bidirectional"))
    )
    (net (code "105") (name "unconnected-(J2-Pada10)") (class "Default")
      (node (ref "J2") (pin "a10") (pinfunction "a10_a10") (pintype "bidirectional"))
    )
    (net (code "106") (name "unconnected-(J2-Padb1)") (class "Default")
      (node (ref "J2") (pin "b1") (pinfunction "b1_b1") (pintype "bidirectional"))
    )
    (net (code "107") (name "unconnected-(J2-Padb2)") (class "Default")
      (node (ref "J2") (pin "b2") (pinfunction "b2_b2") (pintype "bidirectional"))
    )
    (net (code "108") (name "unconnected-(J2-Padb3)") (class "Default")
      (node (ref "J2") (pin "b3") (pinfunction "b3_b3") (pintype "bidirectional"))
    )
    (net (code "109") (name "unconnected-(J2-Padb4)") (class "Default")
      (node (ref "J2") (pin "b4") (pinfunction "b4_b4") (pintype "bidirectional"))
    )
    (net (code "110") (name "unconnected-(J2-Padb6)") (class "Default")
      (node (ref "J2") (pin "b6") (pinfunction "b6_b6") (pintype "bidirectional"))
    )
    (net (code "111") (name "unconnected-(J2-Padb7)") (class "Default")
      (node (ref "J2") (pin "b7") (pinfunction "b7_b7") (pintype "bidirectional"))
    )
    (net (code "112") (name "unconnected-(J2-Padb8)") (class "Default")
      (node (ref "J2") (pin "b8") (pinfunction "b8_b8") (pintype "bidirectional"))
    )
    (net (code "113") (name "unconnected-(J2-Padb10)") (class "Default")
      (node (ref "J2") (pin "b10") (pinfunction "b10_b10") (pintype "bidirectional"))
    )
    (net (code "114") (name "unconnected-(J2-Padd1)") (class "Default")
      (node (ref "J2") (pin "d1") (pinfunction "d1_d1") (pintype "bidirectional"))
    )
    (net (code "115") (name "unconnected-(J2-Padd2)") (class "Default")
      (node (ref "J2") (pin "d2") (pinfunction "d2_d2") (pintype "bidirectional"))
    )
    (net (code "116") (name "unconnected-(J2-Padf1)") (class "Default")
      (node (ref "J2") (pin "f1") (pinfunction "f1_f1") (pintype "bidirectional"))
    )
    (net (code "117") (name "unconnected-(J2-Padf2)") (class "Default")
      (node (ref "J2") (pin "f2") (pinfunction "f2_f2") (pintype "bidirectional"))
    )
    (net (code "118") (name "unconnected-(J6-Pada8)") (class "Default")
      (node (ref "J6") (pin "a8") (pinfunction "a8_a8") (pintype "bidirectional"))
    )
    (net (code "119") (name "unconnected-(J6-Pada9)") (class "Default")
      (node (ref "J6") (pin "a9") (pinfunction "a9_a9") (pintype "bidirectional"))
    )
    (net (code "120") (name "unconnected-(J6-Pada10)") (class "Default")
      (node (ref "J6") (pin "a10") (pinfunction "a10_a10") (pintype "bidirectional"))
    )
    (net (code "121") (name "unconnected-(J6-Padb7)") (class "Default")
      (node (ref "J6") (pin "b7") (pinfunction "b7_b7") (pintype "bidirectional"))
    )
    (net (code "122") (name "unconnected-(J6-Padb8)") (class "Default")
      (node (ref "J6") (pin "b8") (pinfunction "b8_b8") (pintype "bidirectional"))
    )
    (net (code "123") (name "unconnected-(J6-Padb9)") (class "Default")
      (node (ref "J6") (pin "b9") (pinfunction "b9_b9") (pintype "bidirectional"))
    )
    (net (code "124") (name "unconnected-(J6-Padb10)") (class "Default")
      (node (ref "J6") (pin "b10") (pinfunction "b10_b10") (pintype "bidirectional"))
    )
    (net (code "125") (name "unconnected-(J6-Padd5)") (class "Default")
      (node (ref "J6") (pin "d5") (pinfunction "d5_d5") (pintype "bidirectional"))
    )
    (net (code "126") (name "unconnected-(J6-Padd6)") (class "Default")
      (node (ref "J6") (pin "d6") (pinfunction "d6_d6") (pintype "bidirectional"))
    )
    (net (code "127") (name "unconnected-(J6-Padd7)") (class "Default")
      (node (ref "J6") (pin "d7") (pinfunction "d7_d7") (pintype "bidirectional"))
    )
    (net (code "128") (name "unconnected-(J6-Padd8)") (class "Default")
      (node (ref "J6") (pin "d8") (pinfunction "d8_d8") (pintype "bidirectional"))
    )
    (net (code "129") (name "unconnected-(J6-Padd9)") (class "Default")
      (node (ref "J6") (pin "d9") (pinfunction "d9_d9") (pintype "bidirectional"))
    )
    (net (code "130") (name "unconnected-(J6-Padd10)") (class "Default")
      (node (ref "J6") (pin "d10") (pinfunction "d10_d10") (pintype "bidirectional"))
    )
    (net (code "131") (name "unconnected-(J6-Pade1)") (class "Default")
      (node (ref "J6") (pin "e1") (pinfunction "e1_e1") (pintype "bidirectional"))
    )
    (net (code "132") (name "unconnected-(J6-Padf2)") (class "Default")
      (node (ref "J6") (pin "f2") (pinfunction "f2_f2") (pintype "bidirectional"))
    )
  )
)
